# lumiere_ctrl_shematic.net
KiCad netlist of a schematic drawn in Altium Designer
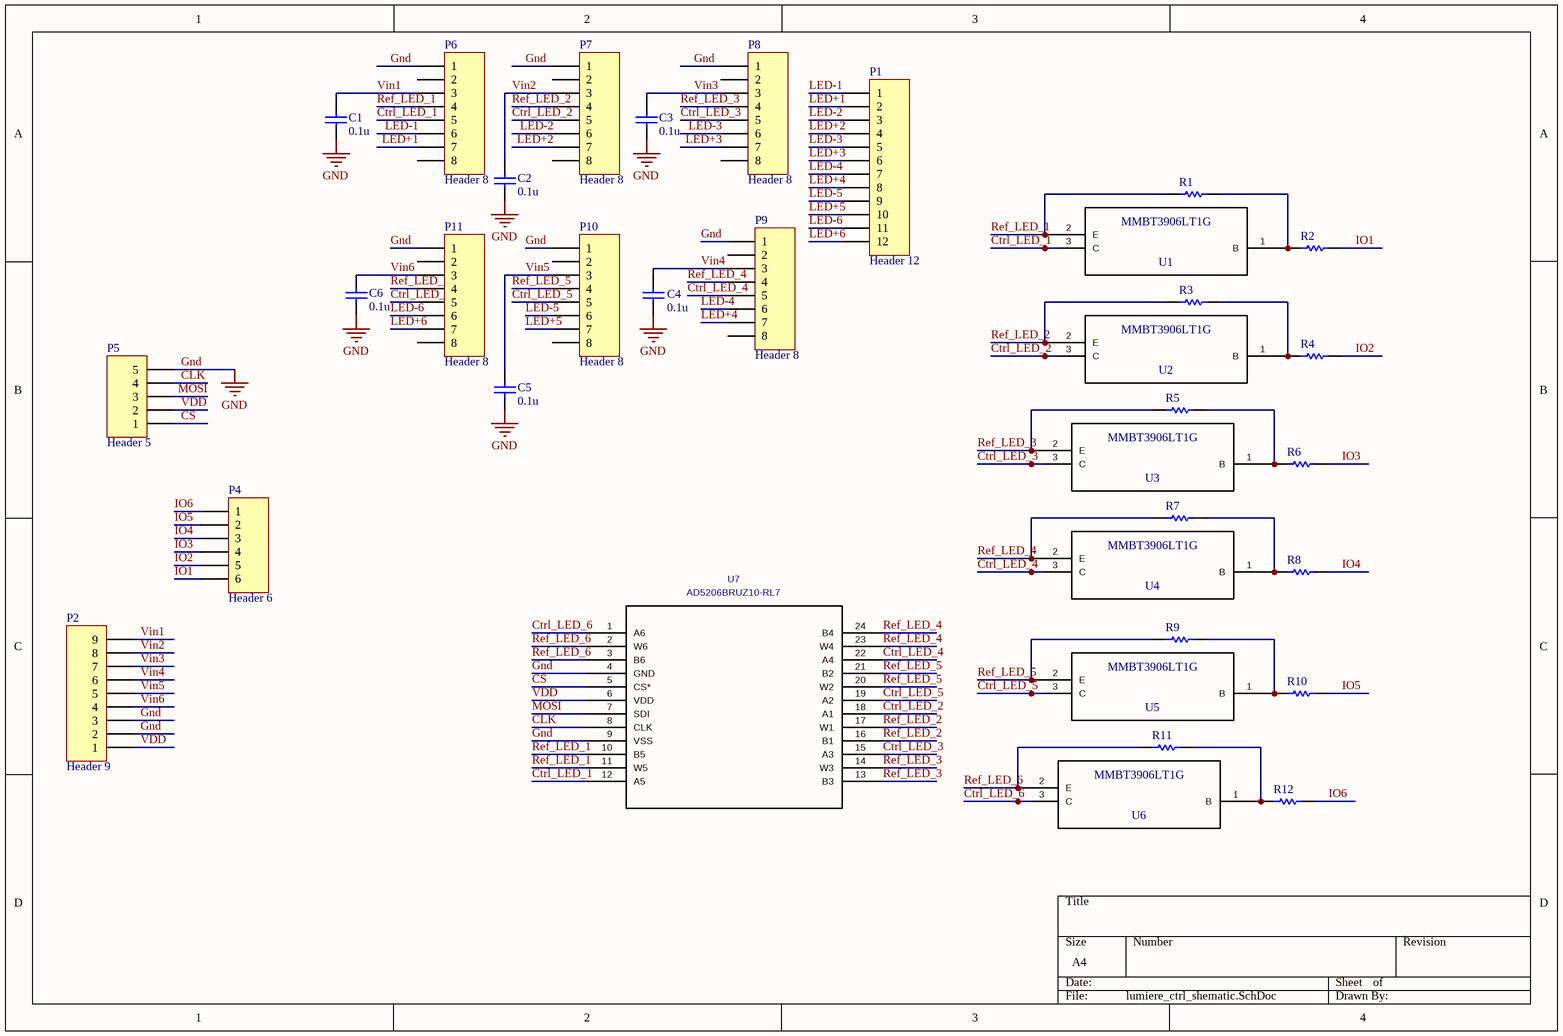
[diagram p0: lumiere_ctrl_shematic.SchDoc]

(export (version "E")
  (design (tool "Eeschema 10.0.6"))
  (components
    (comp (ref "C1")
      (value "0.1u")
      (footprint "CC1206N")
      (description "Capacitor")
      (fields (field (name "VOLTAGE") "50V") (field (name "Comment") "CapSMD"))
      (libsource (lib "S3_projet") (part "CapSMD"))
    )
    (comp (ref "C2")
      (value "0.1u")
      (footprint "CC1206N")
      (description "Capacitor")
      (fields (field (name "VOLTAGE") "50V") (field (name "Comment") "CapSMD"))
      (libsource (lib "S3_projet") (part "CapSMD"))
    )
    (comp (ref "C3")
      (value "0.1u")
      (footprint "CC1206N")
      (description "Capacitor")
      (fields (field (name "VOLTAGE") "50V") (field (name "Comment") "CapSMD"))
      (libsource (lib "S3_projet") (part "CapSMD"))
    )
    (comp (ref "C4")
      (value "0.1u")
      (footprint "CC1206N")
      (description "Capacitor")
      (fields (field (name "VOLTAGE") "50V") (field (name "Comment") "CapSMD"))
      (libsource (lib "S3_projet") (part "CapSMD"))
    )
    (comp (ref "C5")
      (value "0.1u")
      (footprint "CC1206N")
      (description "Capacitor")
      (fields (field (name "VOLTAGE") "50V") (field (name "Comment") "CapSMD"))
      (libsource (lib "S3_projet") (part "CapSMD"))
    )
    (comp (ref "C6")
      (value "0.1u")
      (footprint "CC1206N")
      (description "Capacitor")
      (fields (field (name "VOLTAGE") "50V") (field (name "Comment") "CapSMD"))
      (libsource (lib "S3_projet") (part "CapSMD"))
    )
    (comp (ref "P1")
      (value "Header 12")
      (footprint "Terminal block 12 pos")
      (description "Header, 12-Pin")
      (fields (field (name "PUBLISHER") "Altium Limited"))
      (libsource (lib "Miscellaneous Connectors") (part "Header 12"))
    )
    (comp (ref "P2")
      (value "Header 9")
      (footprint "Terminal block 9 pos")
      (description "Header, 9-Pin")
      (fields (field (name "PUBLISHER") "Altium Limited"))
      (libsource (lib "Miscellaneous Connectors") (part "Header 9"))
    )
    (comp (ref "P4")
      (value "Header 6")
      (footprint "HDR1X6")
      (description "Header, 6-Pin")
      (fields (field (name "PUBLISHER") "Altium Limited"))
      (libsource (lib "Miscellaneous Connectors") (part "Header 6"))
    )
    (comp (ref "P5")
      (value "Header 5")
      (footprint "HDR1X5")
      (description "Header, 5-Pin")
      (fields (field (name "PUBLISHER") "Altium Limited"))
      (libsource (lib "Miscellaneous Connectors") (part "Header 5"))
    )
    (comp (ref "P6")
      (value "Header 8")
      (footprint "HDR1X8")
      (description "Header, 8-Pin")
      (fields (field (name "PUBLISHER") "Altium Limited"))
      (libsource (lib "Miscellaneous Connectors") (part "Header 8"))
    )
    (comp (ref "P7")
      (value "Header 8")
      (footprint "HDR1X8")
      (description "Header, 8-Pin")
      (fields (field (name "PUBLISHER") "Altium Limited"))
      (libsource (lib "Miscellaneous Connectors") (part "Header 8"))
    )
    (comp (ref "P8")
      (value "Header 8")
      (footprint "HDR1X8")
      (description "Header, 8-Pin")
      (fields (field (name "PUBLISHER") "Altium Limited"))
      (libsource (lib "Miscellaneous Connectors") (part "Header 8"))
    )
    (comp (ref "P9")
      (value "Header 8")
      (footprint "HDR1X8")
      (description "Header, 8-Pin")
      (fields (field (name "PUBLISHER") "Altium Limited"))
      (libsource (lib "Miscellaneous Connectors") (part "Header 8"))
    )
    (comp (ref "P10")
      (value "Header 8")
      (footprint "HDR1X8")
      (description "Header, 8-Pin")
      (fields (field (name "PUBLISHER") "Altium Limited"))
      (libsource (lib "Miscellaneous Connectors") (part "Header 8"))
    )
    (comp (ref "P11")
      (value "Header 8")
      (footprint "HDR1X8")
      (description "Header, 8-Pin")
      (fields (field (name "PUBLISHER") "Altium Limited"))
      (libsource (lib "Miscellaneous Connectors") (part "Header 8"))
    )
    (comp (ref "R1")
      (value "ResSMD")
      (footprint "STA_RMCF1206")
      (libsource (lib "S3_projet") (part "ResSMD"))
    )
    (comp (ref "R2")
      (value "ResSMD")
      (footprint "STA_RMCF1206")
      (libsource (lib "S3_projet") (part "ResSMD"))
    )
    (comp (ref "R3")
      (value "ResSMD")
      (footprint "STA_RMCF1206")
      (libsource (lib "S3_projet") (part "ResSMD"))
    )
    (comp (ref "R4")
      (value "ResSMD")
      (footprint "STA_RMCF1206")
      (libsource (lib "S3_projet") (part "ResSMD"))
    )
    (comp (ref "R5")
      (value "ResSMD")
      (footprint "STA_RMCF1206")
      (libsource (lib "S3_projet") (part "ResSMD"))
    )
    (comp (ref "R6")
      (value "ResSMD")
      (footprint "STA_RMCF1206")
      (libsource (lib "S3_projet") (part "ResSMD"))
    )
    (comp (ref "R7")
      (value "ResSMD")
      (footprint "STA_RMCF1206")
      (libsource (lib "S3_projet") (part "ResSMD"))
    )
    (comp (ref "R8")
      (value "ResSMD")
      (footprint "STA_RMCF1206")
      (libsource (lib "S3_projet") (part "ResSMD"))
    )
    (comp (ref "R9")
      (value "ResSMD")
      (footprint "STA_RMCF1206")
      (libsource (lib "S3_projet") (part "ResSMD"))
    )
    (comp (ref "R10")
      (value "ResSMD")
      (footprint "STA_RMCF1206")
      (libsource (lib "S3_projet") (part "ResSMD"))
    )
    (comp (ref "R11")
      (value "ResSMD")
      (footprint "STA_RMCF1206")
      (libsource (lib "S3_projet") (part "ResSMD"))
    )
    (comp (ref "R12")
      (value "ResSMD")
      (footprint "STA_RMCF1206")
      (libsource (lib "S3_projet") (part "ResSMD"))
    )
    (comp (ref "U1")
      (value "MMBT3906LT1G")
      (footprint "SOT-23")
      (libsource (lib "AltiumV15") (part "MMBT3906LT1G"))
    )
    (comp (ref "U2")
      (value "MMBT3906LT1G")
      (footprint "SOT-23")
      (libsource (lib "AltiumV15") (part "MMBT3906LT1G"))
    )
    (comp (ref "U3")
      (value "MMBT3906LT1G")
      (footprint "SOT-23")
      (libsource (lib "AltiumV15") (part "MMBT3906LT1G"))
    )
    (comp (ref "U4")
      (value "MMBT3906LT1G")
      (footprint "SOT-23")
      (libsource (lib "AltiumV15") (part "MMBT3906LT1G"))
    )
    (comp (ref "U5")
      (value "MMBT3906LT1G")
      (footprint "SOT-23")
      (libsource (lib "AltiumV15") (part "MMBT3906LT1G"))
    )
    (comp (ref "U6")
      (value "MMBT3906LT1G")
      (footprint "SOT-23")
      (libsource (lib "AltiumV15") (part "MMBT3906LT1G"))
    )
    (comp (ref "U7")
      (value "AD5206BRUZ10-RL7")
      (footprint "RU_24")
      (libsource (lib "AltiumV15") (part "AD5206BRUZ10-RL7"))
    )
  )
  (nets
    (net (code "1") (name "/CLK") (class "Default")
      (node (ref "P5") (pin "4") (pinfunction "4_4") (pintype "passive"))
      (node (ref "U7") (pin "8") (pinfunction "CLK_8") (pintype "passive"))
    )
    (net (code "2") (name "/CS") (class "Default")
      (node (ref "P5") (pin "1") (pinfunction "1_1") (pintype "passive"))
      (node (ref "U7") (pin "5") (pinfunction "CS*_5") (pintype "passive"))
    )
    (net (code "3") (name "/Ctrl_LED_1") (class "Default")
      (node (ref "P6") (pin "5") (pinfunction "5_5") (pintype "passive"))
      (node (ref "U1") (pin "3") (pinfunction "C_3") (pintype "passive"))
      (node (ref "U7") (pin "12") (pinfunction "A5_12") (pintype "passive"))
    )
    (net (code "4") (name "/Ctrl_LED_2") (class "Default")
      (node (ref "P7") (pin "5") (pinfunction "5_5") (pintype "passive"))
      (node (ref "U2") (pin "3") (pinfunction "C_3") (pintype "passive"))
      (node (ref "U7") (pin "18") (pinfunction "A1_18") (pintype "passive"))
    )
    (net (code "5") (name "/Ctrl_LED_3") (class "Default")
      (node (ref "P8") (pin "5") (pinfunction "5_5") (pintype "passive"))
      (node (ref "U3") (pin "3") (pinfunction "C_3") (pintype "passive"))
      (node (ref "U7") (pin "15") (pinfunction "A3_15") (pintype "passive"))
    )
    (net (code "6") (name "/Ctrl_LED_4") (class "Default")
      (node (ref "P9") (pin "5") (pinfunction "5_5") (pintype "passive"))
      (node (ref "U4") (pin "3") (pinfunction "C_3") (pintype "passive"))
      (node (ref "U7") (pin "22") (pinfunction "A4_22") (pintype "passive"))
    )
    (net (code "7") (name "/Ctrl_LED_5") (class "Default")
      (node (ref "P10") (pin "5") (pinfunction "5_5") (pintype "passive"))
      (node (ref "U5") (pin "3") (pinfunction "C_3") (pintype "passive"))
      (node (ref "U7") (pin "19") (pinfunction "A2_19") (pintype "passive"))
    )
    (net (code "8") (name "/Ctrl_LED_6") (class "Default")
      (node (ref "P11") (pin "5") (pinfunction "5_5") (pintype "passive"))
      (node (ref "U6") (pin "3") (pinfunction "C_3") (pintype "passive"))
      (node (ref "U7") (pin "1") (pinfunction "A6_1") (pintype "passive"))
    )
    (net (code "9") (name "/IO1") (class "Default")
      (node (ref "P4") (pin "6") (pinfunction "6_6") (pintype "passive"))
      (node (ref "R2") (pin "1") (pinfunction "1_1") (pintype "passive"))
    )
    (net (code "10") (name "/IO2") (class "Default")
      (node (ref "P4") (pin "5") (pinfunction "5_5") (pintype "passive"))
      (node (ref "R4") (pin "1") (pinfunction "1_1") (pintype "passive"))
    )
    (net (code "11") (name "/IO3") (class "Default")
      (node (ref "P4") (pin "4") (pinfunction "4_4") (pintype "passive"))
      (node (ref "R6") (pin "1") (pinfunction "1_1") (pintype "passive"))
    )
    (net (code "12") (name "/IO4") (class "Default")
      (node (ref "P4") (pin "3") (pinfunction "3_3") (pintype "passive"))
      (node (ref "R8") (pin "1") (pinfunction "1_1") (pintype "passive"))
    )
    (net (code "13") (name "/IO5") (class "Default")
      (node (ref "P4") (pin "2") (pinfunction "2_2") (pintype "passive"))
      (node (ref "R10") (pin "1") (pinfunction "1_1") (pintype "passive"))
    )
    (net (code "14") (name "/IO6") (class "Default")
      (node (ref "P4") (pin "1") (pinfunction "1_1") (pintype "passive"))
      (node (ref "R12") (pin "1") (pinfunction "1_1") (pintype "passive"))
    )
    (net (code "15") (name "/LED+1") (class "Default")
      (node (ref "P1") (pin "2") (pinfunction "2_2") (pintype "passive"))
      (node (ref "P6") (pin "7") (pinfunction "7_7") (pintype "passive"))
    )
    (net (code "16") (name "/LED+2") (class "Default")
      (node (ref "P1") (pin "4") (pinfunction "4_4") (pintype "passive"))
      (node (ref "P7") (pin "7") (pinfunction "7_7") (pintype "passive"))
    )
    (net (code "17") (name "/LED+3") (class "Default")
      (node (ref "P1") (pin "6") (pinfunction "6_6") (pintype "passive"))
      (node (ref "P8") (pin "7") (pinfunction "7_7") (pintype "passive"))
    )
    (net (code "18") (name "/LED+4") (class "Default")
      (node (ref "P1") (pin "8") (pinfunction "8_8") (pintype "passive"))
      (node (ref "P9") (pin "7") (pinfunction "7_7") (pintype "passive"))
    )
    (net (code "19") (name "/LED+5") (class "Default")
      (node (ref "P1") (pin "10") (pinfunction "10_10") (pintype "passive"))
      (node (ref "P10") (pin "7") (pinfunction "7_7") (pintype "passive"))
    )
    (net (code "20") (name "/LED+6") (class "Default")
      (node (ref "P1") (pin "12") (pinfunction "12_12") (pintype "passive"))
      (node (ref "P11") (pin "7") (pinfunction "7_7") (pintype "passive"))
    )
    (net (code "21") (name "/LED-1") (class "Default")
      (node (ref "P1") (pin "1") (pinfunction "1_1") (pintype "passive"))
      (node (ref "P6") (pin "6") (pinfunction "6_6") (pintype "passive"))
    )
    (net (code "22") (name "/LED-2") (class "Default")
      (node (ref "P1") (pin "3") (pinfunction "3_3") (pintype "passive"))
      (node (ref "P7") (pin "6") (pinfunction "6_6") (pintype "passive"))
    )
    (net (code "23") (name "/LED-3") (class "Default")
      (node (ref "P1") (pin "5") (pinfunction "5_5") (pintype "passive"))
      (node (ref "P8") (pin "6") (pinfunction "6_6") (pintype "passive"))
    )
    (net (code "24") (name "/LED-4") (class "Default")
      (node (ref "P1") (pin "7") (pinfunction "7_7") (pintype "passive"))
      (node (ref "P9") (pin "6") (pinfunction "6_6") (pintype "passive"))
    )
    (net (code "25") (name "/LED-5") (class "Default")
      (node (ref "P1") (pin "9") (pinfunction "9_9") (pintype "passive"))
      (node (ref "P10") (pin "6") (pinfunction "6_6") (pintype "passive"))
    )
    (net (code "26") (name "/LED-6") (class "Default")
      (node (ref "P1") (pin "11") (pinfunction "11_11") (pintype "passive"))
      (node (ref "P11") (pin "6") (pinfunction "6_6") (pintype "passive"))
    )
    (net (code "27") (name "/MOSI") (class "Default")
      (node (ref "P5") (pin "3") (pinfunction "3_3") (pintype "passive"))
      (node (ref "U7") (pin "7") (pinfunction "SDI_7") (pintype "passive"))
    )
    (net (code "28") (name "/Ref_LED_1") (class "Default")
      (node (ref "P6") (pin "4") (pinfunction "4_4") (pintype "passive"))
      (node (ref "R1") (pin "2") (pinfunction "2_2") (pintype "passive"))
      (node (ref "U1") (pin "2") (pinfunction "E_2") (pintype "passive"))
      (node (ref "U7") (pin "10") (pinfunction "B5_10") (pintype "passive"))
      (node (ref "U7") (pin "11") (pinfunction "W5_11") (pintype "passive"))
    )
    (net (code "29") (name "/Ref_LED_2") (class "Default")
      (node (ref "P7") (pin "4") (pinfunction "4_4") (pintype "passive"))
      (node (ref "R3") (pin "2") (pinfunction "2_2") (pintype "passive"))
      (node (ref "U2") (pin "2") (pinfunction "E_2") (pintype "passive"))
      (node (ref "U7") (pin "16") (pinfunction "B1_16") (pintype "passive"))
      (node (ref "U7") (pin "17") (pinfunction "W1_17") (pintype "passive"))
    )
    (net (code "30") (name "/Ref_LED_3") (class "Default")
      (node (ref "P8") (pin "4") (pinfunction "4_4") (pintype "passive"))
      (node (ref "R5") (pin "2") (pinfunction "2_2") (pintype "passive"))
      (node (ref "U3") (pin "2") (pinfunction "E_2") (pintype "passive"))
      (node (ref "U7") (pin "13") (pinfunction "B3_13") (pintype "passive"))
      (node (ref "U7") (pin "14") (pinfunction "W3_14") (pintype "passive"))
    )
    (net (code "31") (name "/Ref_LED_4") (class "Default")
      (node (ref "P9") (pin "4") (pinfunction "4_4") (pintype "passive"))
      (node (ref "R7") (pin "2") (pinfunction "2_2") (pintype "passive"))
      (node (ref "U4") (pin "2") (pinfunction "E_2") (pintype "passive"))
      (node (ref "U7") (pin "23") (pinfunction "W4_23") (pintype "passive"))
      (node (ref "U7") (pin "24") (pinfunction "B4_24") (pintype "passive"))
    )
    (net (code "32") (name "/Ref_LED_5") (class "Default")
      (node (ref "P10") (pin "4") (pinfunction "4_4") (pintype "passive"))
      (node (ref "R9") (pin "2") (pinfunction "2_2") (pintype "passive"))
      (node (ref "U5") (pin "2") (pinfunction "E_2") (pintype "passive"))
      (node (ref "U7") (pin "20") (pinfunction "W2_20") (pintype "passive"))
      (node (ref "U7") (pin "21") (pinfunction "B2_21") (pintype "passive"))
    )
    (net (code "33") (name "/Ref_LED_6") (class "Default")
      (node (ref "P11") (pin "4") (pinfunction "4_4") (pintype "passive"))
      (node (ref "R11") (pin "2") (pinfunction "2_2") (pintype "passive"))
      (node (ref "U6") (pin "2") (pinfunction "E_2") (pintype "passive"))
      (node (ref "U7") (pin "2") (pinfunction "W6_2") (pintype "passive"))
      (node (ref "U7") (pin "3") (pinfunction "B6_3") (pintype "passive"))
    )
    (net (code "34") (name "/VDD") (class "Default")
      (node (ref "P2") (pin "1") (pinfunction "1_1") (pintype "passive"))
      (node (ref "P5") (pin "2") (pinfunction "2_2") (pintype "passive"))
      (node (ref "U7") (pin "6") (pinfunction "VDD_6") (pintype "power_in"))
    )
    (net (code "35") (name "/Vin1") (class "Default")
      (node (ref "C1") (pin "2") (pinfunction "2_2") (pintype "passive"))
      (node (ref "P2") (pin "9") (pinfunction "9_9") (pintype "passive"))
      (node (ref "P6") (pin "3") (pinfunction "3_3") (pintype "passive"))
    )
    (net (code "36") (name "/Vin2") (class "Default")
      (node (ref "C2") (pin "2") (pinfunction "2_2") (pintype "passive"))
      (node (ref "P2") (pin "8") (pinfunction "8_8") (pintype "passive"))
      (node (ref "P7") (pin "3") (pinfunction "3_3") (pintype "passive"))
    )
    (net (code "37") (name "/Vin3") (class "Default")
      (node (ref "C3") (pin "2") (pinfunction "2_2") (pintype "passive"))
      (node (ref "P2") (pin "7") (pinfunction "7_7") (pintype "passive"))
      (node (ref "P8") (pin "3") (pinfunction "3_3") (pintype "passive"))
    )
    (net (code "38") (name "/Vin4") (class "Default")
      (node (ref "C4") (pin "2") (pinfunction "2_2") (pintype "passive"))
      (node (ref "P2") (pin "6") (pinfunction "6_6") (pintype "passive"))
      (node (ref "P9") (pin "3") (pinfunction "3_3") (pintype "passive"))
    )
    (net (code "39") (name "/Vin5") (class "Default")
      (node (ref "C5") (pin "2") (pinfunction "2_2") (pintype "passive"))
      (node (ref "P10") (pin "3") (pinfunction "3_3") (pintype "passive"))
      (node (ref "P2") (pin "5") (pinfunction "5_5") (pintype "passive"))
    )
    (net (code "40") (name "/Vin6") (class "Default")
      (node (ref "C6") (pin "2") (pinfunction "2_2") (pintype "passive"))
      (node (ref "P11") (pin "3") (pinfunction "3_3") (pintype "passive"))
      (node (ref "P2") (pin "4") (pinfunction "4_4") (pintype "passive"))
    )
    (net (code "41") (name "GND") (class "Default")
      (node (ref "C1") (pin "1") (pinfunction "1_1") (pintype "passive"))
      (node (ref "C2") (pin "1") (pinfunction "1_1") (pintype "passive"))
      (node (ref "C3") (pin "1") (pinfunction "1_1") (pintype "passive"))
      (node (ref "C4") (pin "1") (pinfunction "1_1") (pintype "passive"))
      (node (ref "C5") (pin "1") (pinfunction "1_1") (pintype "passive"))
      (node (ref "C6") (pin "1") (pinfunction "1_1") (pintype "passive"))
      (node (ref "P10") (pin "1") (pinfunction "1_1") (pintype "passive"))
      (node (ref "P11") (pin "1") (pinfunction "1_1") (pintype "passive"))
      (node (ref "P2") (pin "2") (pinfunction "2_2") (pintype "passive"))
      (node (ref "P2") (pin "3") (pinfunction "3_3") (pintype "passive"))
      (node (ref "P5") (pin "5") (pinfunction "5_5") (pintype "passive"))
      (node (ref "P6") (pin "1") (pinfunction "1_1") (pintype "passive"))
      (node (ref "P7") (pin "1") (pinfunction "1_1") (pintype "passive"))
      (node (ref "P8") (pin "1") (pinfunction "1_1") (pintype "passive"))
      (node (ref "P9") (pin "1") (pinfunction "1_1") (pintype "passive"))
      (node (ref "U7") (pin "4") (pinfunction "GND_4") (pintype "passive"))
      (node (ref "U7") (pin "9") (pinfunction "VSS_9") (pintype "power_in"))
    )
    (net (code "42") (name "Net-(U1-B)") (class "Default")
      (node (ref "R1") (pin "1") (pinfunction "1_1") (pintype "passive"))
      (node (ref "R2") (pin "2") (pinfunction "2_2") (pintype "passive"))
      (node (ref "U1") (pin "1") (pinfunction "B_1") (pintype "passive"))
    )
    (net (code "43") (name "Net-(U2-B)") (class "Default")
      (node (ref "R3") (pin "1") (pinfunction "1_1") (pintype "passive"))
      (node (ref "R4") (pin "2") (pinfunction "2_2") (pintype "passive"))
      (node (ref "U2") (pin "1") (pinfunction "B_1") (pintype "passive"))
    )
    (net (code "44") (name "Net-(U3-B)") (class "Default")
      (node (ref "R5") (pin "1") (pinfunction "1_1") (pintype "passive"))
      (node (ref "R6") (pin "2") (pinfunction "2_2") (pintype "passive"))
      (node (ref "U3") (pin "1") (pinfunction "B_1") (pintype "passive"))
    )
    (net (code "45") (name "Net-(U4-B)") (class "Default")
      (node (ref "R7") (pin "1") (pinfunction "1_1") (pintype "passive"))
      (node (ref "R8") (pin "2") (pinfunction "2_2") (pintype "passive"))
      (node (ref "U4") (pin "1") (pinfunction "B_1") (pintype "passive"))
    )
    (net (code "46") (name "Net-(U5-B)") (class "Default")
      (node (ref "R10") (pin "2") (pinfunction "2_2") (pintype "passive"))
      (node (ref "R9") (pin "1") (pinfunction "1_1") (pintype "passive"))
      (node (ref "U5") (pin "1") (pinfunction "B_1") (pintype "passive"))
    )
    (net (code "47") (name "Net-(U6-B)") (class "Default")
      (node (ref "R11") (pin "1") (pinfunction "1_1") (pintype "passive"))
      (node (ref "R12") (pin "2") (pinfunction "2_2") (pintype "passive"))
      (node (ref "U6") (pin "1") (pinfunction "B_1") (pintype "passive"))
    )
    (net (code "48") (name "unconnected-(P6-Pad2)") (class "Default")
      (node (ref "P6") (pin "2") (pinfunction "2_2") (pintype "passive"))
    )
    (net (code "49") (name "unconnected-(P6-Pad8)") (class "Default")
      (node (ref "P6") (pin "8") (pinfunction "8_8") (pintype "passive"))
    )
    (net (code "50") (name "unconnected-(P7-Pad2)") (class "Default")
      (node (ref "P7") (pin "2") (pinfunction "2_2") (pintype "passive"))
    )
    (net (code "51") (name "unconnected-(P7-Pad8)") (class "Default")
      (node (ref "P7") (pin "8") (pinfunction "8_8") (pintype "passive"))
    )
    (net (code "52") (name "unconnected-(P8-Pad2)") (class "Default")
      (node (ref "P8") (pin "2") (pinfunction "2_2") (pintype "passive"))
    )
    (net (code "53") (name "unconnected-(P8-Pad8)") (class "Default")
      (node (ref "P8") (pin "8") (pinfunction "8_8") (pintype "passive"))
    )
    (net (code "54") (name "unconnected-(P9-Pad2)") (class "Default")
      (node (ref "P9") (pin "2") (pinfunction "2_2") (pintype "passive"))
    )
    (net (code "55") (name "unconnected-(P9-Pad8)") (class "Default")
      (node (ref "P9") (pin "8") (pinfunction "8_8") (pintype "passive"))
    )
    (net (code "56") (name "unconnected-(P10-Pad2)") (class "Default")
      (node (ref "P10") (pin "2") (pinfunction "2_2") (pintype "passive"))
    )
    (net (code "57") (name "unconnected-(P10-Pad8)") (class "Default")
      (node (ref "P10") (pin "8") (pinfunction "8_8") (pintype "passive"))
    )
    (net (code "58") (name "unconnected-(P11-Pad2)") (class "Default")
      (node (ref "P11") (pin "2") (pinfunction "2_2") (pintype "passive"))
    )
    (net (code "59") (name "unconnected-(P11-Pad8)") (class "Default")
      (node (ref "P11") (pin "8") (pinfunction "8_8") (pintype "passive"))
    )
  )
)
